# blue-jammer.net
KiCad netlist of a schematic drawn in EasyEDA
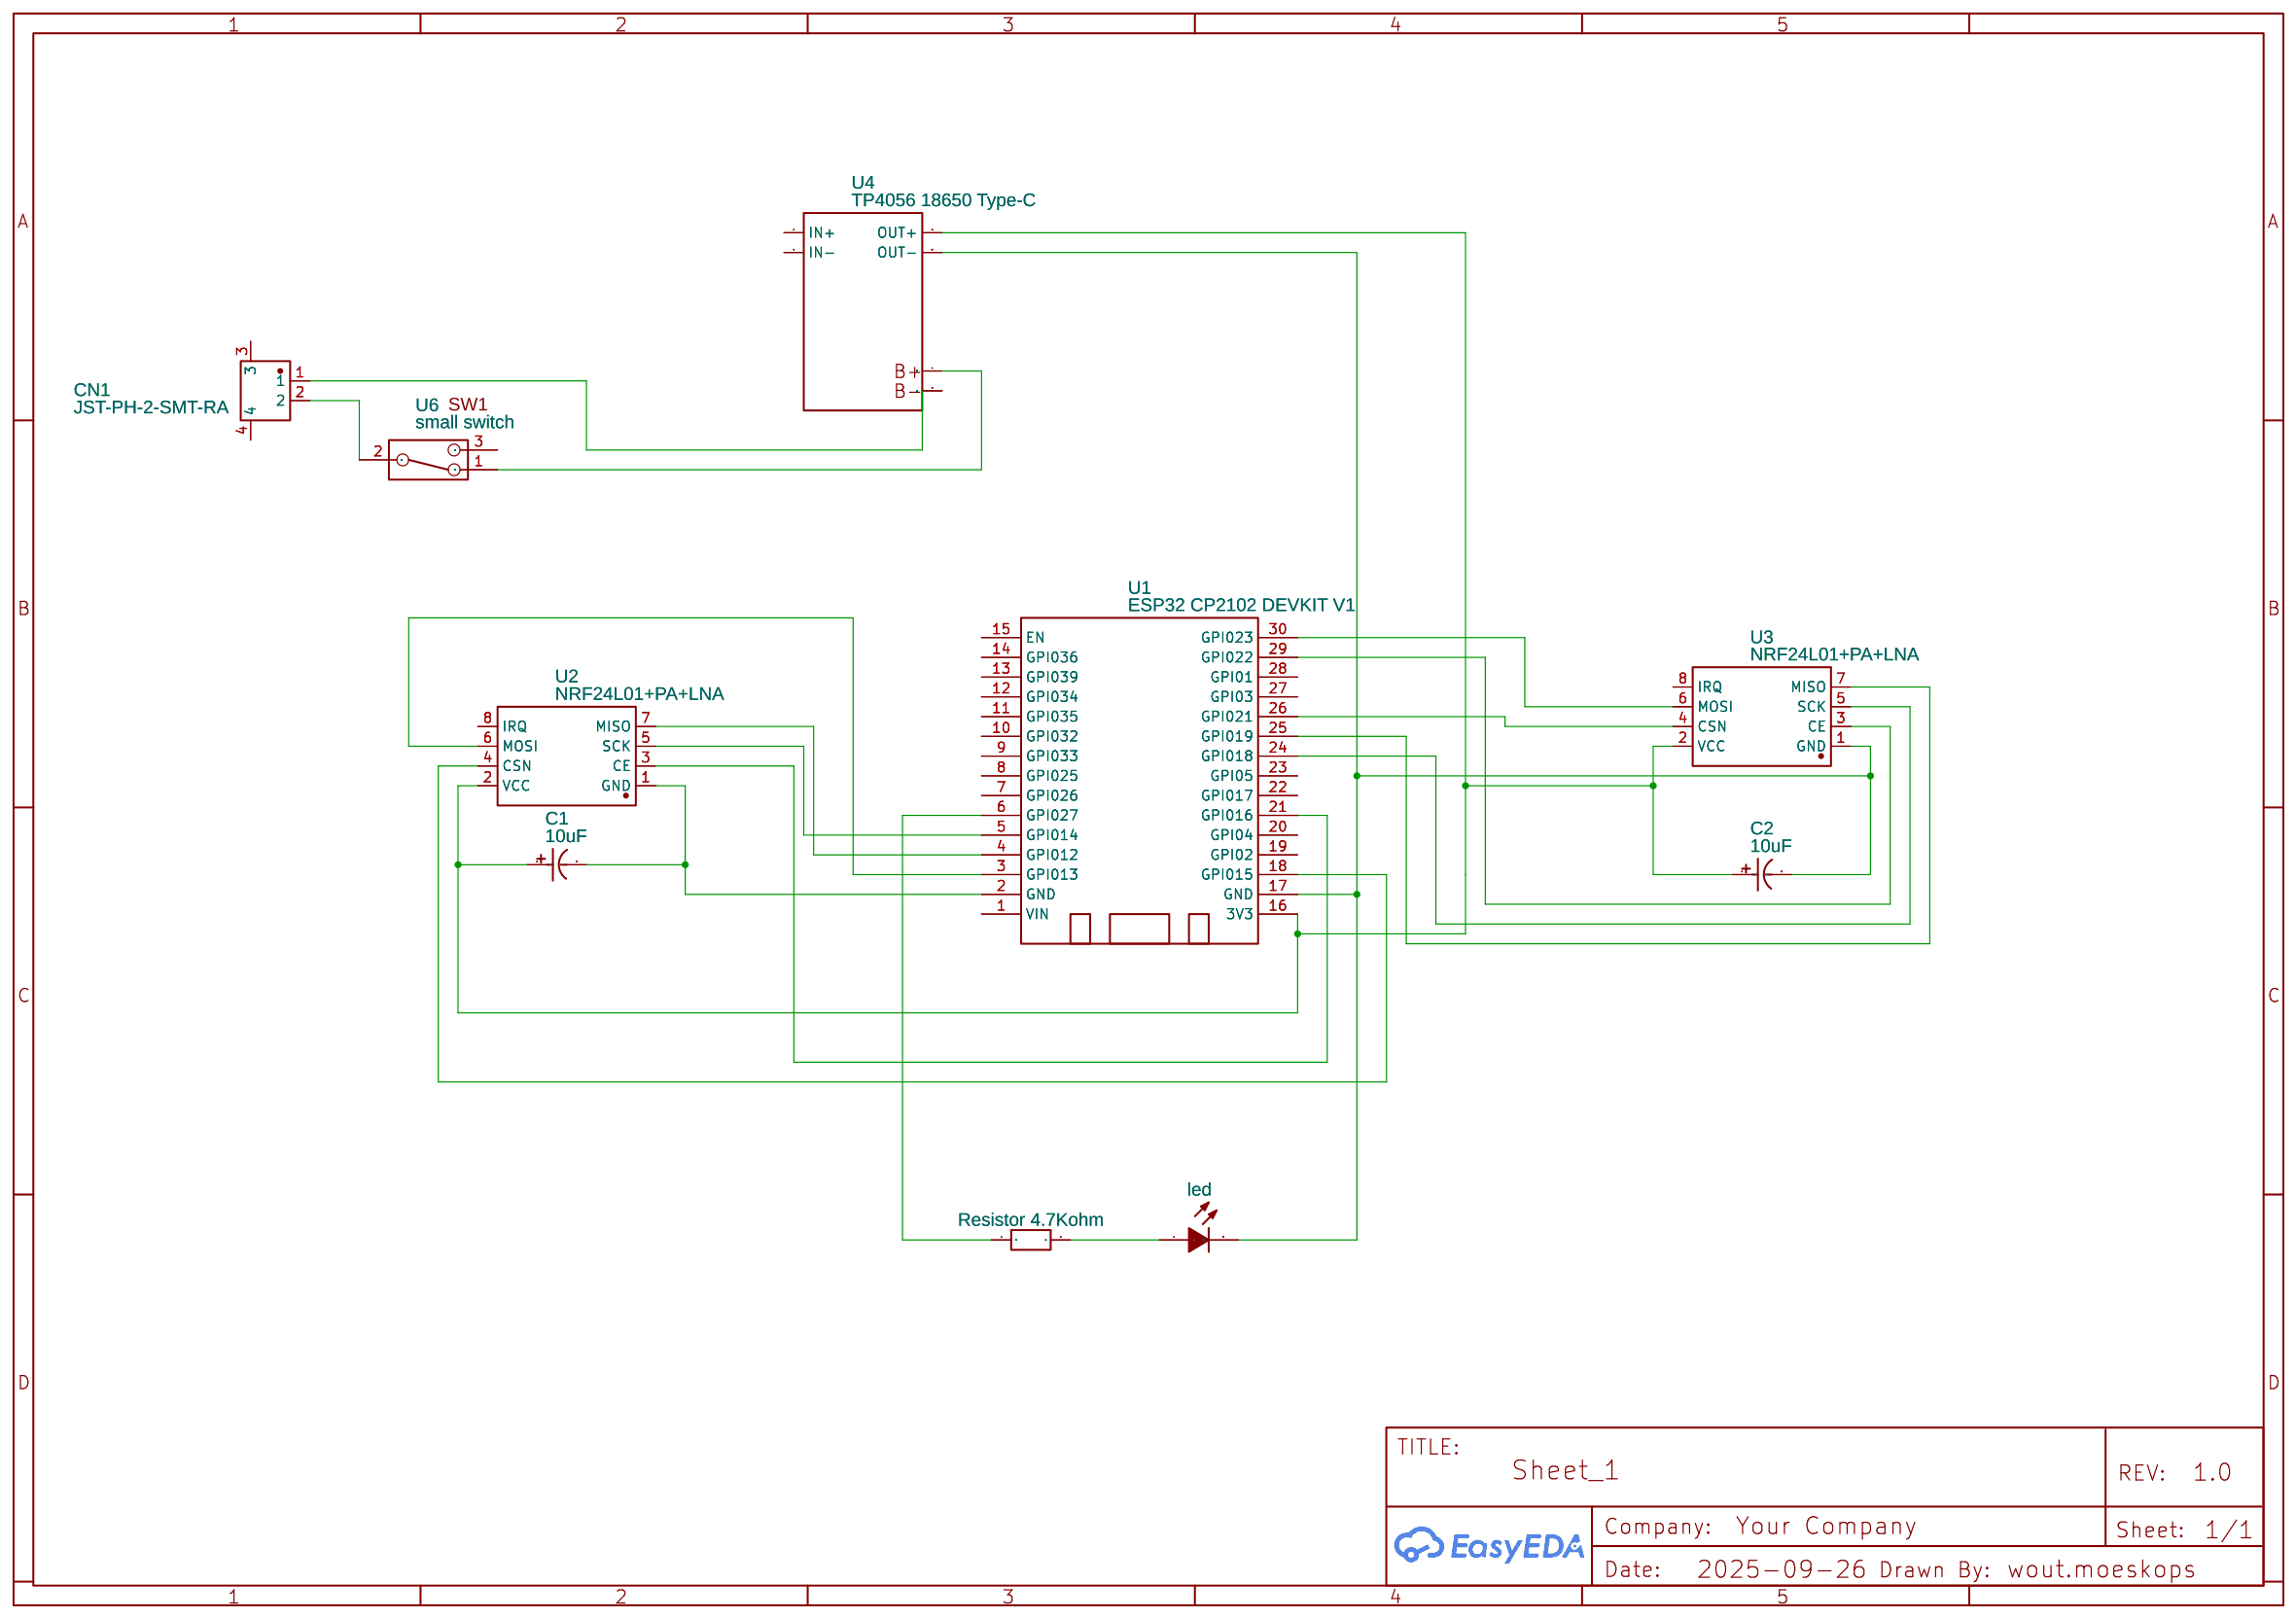
[diagram p0: schematic sheet]

(export (version "E")
  (design (tool "Eeschema 10.0.6"))
  (components
    (comp (ref "C1")
      (value "10uF")
      (fields
        (field (name "Manufacturer Part") "electrolytic capacitor10UF50V")
        (field (name "Manufacturer") "ValuePro")
      )
      (libsource (lib "") (part "10UF 50V CAPACITOR"))
    )
    (comp (ref "C2")
      (value "10uF")
      (fields
        (field (name "Manufacturer Part") "electrolytic capacitor10UF50V")
        (field (name "Manufacturer") "ValuePro")
      )
      (libsource (lib "") (part "10UF 50V CAPACITOR"))
    )
    (comp (ref "CN1") (value "JST-PH-2-SMT-RA") (libsource (lib "") (part "JST-PH-2-SMT-RA")))
    (comp (ref "D2")
      (value "led")
      (fields (field (name "Manufacturer Part") "5600") (field (name "Manufacturer") "VccLite"))
      (libsource (lib "") (part "3mm Green TH LED 5600"))
    )
    (comp (ref "R2")
      (value "Resistor 4.7Kohm")
      (fields (field (name "Manufacturer Part") "EWWR0001J20R0T9") (field (name "Manufacturer") "1"))
      (libsource (lib "") (part "560_Axial_1.2W1%_Tha_239"))
    )
    (comp (ref "U1") (value "ESP32 CP2102 DEVKIT V1") (libsource (lib "") (part "ESP32 CP2102 DEVKIT V1")))
    (comp (ref "U2")
      (value "NRF24L01+PA+LNA")
      (fields (field (name "Manufacturer Part") "nRF24L01+PA+LNA"))
      (libsource (lib "") (part "NRF24L01+PA+LNA"))
    )
    (comp (ref "U3")
      (value "NRF24L01+PA+LNA")
      (fields (field (name "Manufacturer Part") "nRF24L01+PA+LNA"))
      (libsource (lib "") (part "NRF24L01+PA+LNA"))
    )
    (comp (ref "U4") (value "TP4056 18650 Type-C") (libsource (lib "") (part "TP4056 18650 Type-C")))
    (comp (ref "U6") (value "small switch") (libsource (lib "") (part "small switch")))
  )
  (nets
    (net (code "1") (name "Net-(C1-+)") (class "Default")
      (node (ref "C1") (pin "1") (pinfunction "+_1") (pintype "input"))
      (node (ref "C2") (pin "1") (pinfunction "+_1") (pintype "input"))
      (node (ref "U1") (pin "16") (pinfunction "3V3_16") (pintype "bidirectional"))
      (node (ref "U2") (pin "2") (pinfunction "VCC_2") (pintype "unspecified"))
      (node (ref "U3") (pin "2") (pinfunction "VCC_2") (pintype "unspecified"))
      (node (ref "U4") (pin "3") (pinfunction "OUT+_3") (pintype "passive"))
    )
    (net (code "2") (name "Net-(C1--)") (class "Default")
      (node (ref "C1") (pin "2") (pinfunction "-_2") (pintype "input"))
      (node (ref "U1") (pin "2") (pinfunction "GND_2") (pintype "bidirectional"))
      (node (ref "U2") (pin "1") (pinfunction "GND_1") (pintype "unspecified"))
    )
    (net (code "3") (name "Net-(C2--)") (class "Default")
      (node (ref "C2") (pin "2") (pinfunction "-_2") (pintype "input"))
      (node (ref "D2") (pin "2") (pinfunction "K_2") (pintype "input"))
      (node (ref "U1") (pin "17") (pinfunction "GND_17") (pintype "bidirectional"))
      (node (ref "U3") (pin "1") (pinfunction "GND_1") (pintype "unspecified"))
      (node (ref "U4") (pin "6") (pinfunction "OUT-_6") (pintype "passive"))
    )
    (net (code "4") (name "Net-(CN1-Pad2)") (class "Default")
      (node (ref "CN1") (pin "2") (pinfunction "2_2") (pintype "unspecified"))
      (node (ref "U6") (pin "2") (pinfunction "2_2") (pintype "unspecified"))
    )
    (net (code "5") (name "Net-(D2-A)") (class "Default")
      (node (ref "D2") (pin "1") (pinfunction "A_1") (pintype "input"))
      (node (ref "R2") (pin "2") (pinfunction "2_2") (pintype "unspecified"))
    )
    (net (code "6") (name "Net-(U1-GPI012)") (class "Default")
      (node (ref "U1") (pin "4") (pinfunction "GPI012_4") (pintype "bidirectional"))
      (node (ref "U2") (pin "7") (pinfunction "MISO_7") (pintype "unspecified"))
    )
    (net (code "7") (name "Net-(U1-GPI013)") (class "Default")
      (node (ref "U1") (pin "3") (pinfunction "GPI013_3") (pintype "bidirectional"))
      (node (ref "U2") (pin "6") (pinfunction "MOSI_6") (pintype "unspecified"))
    )
    (net (code "8") (name "Net-(U1-GPI014)") (class "Default")
      (node (ref "U1") (pin "5") (pinfunction "GPI014_5") (pintype "bidirectional"))
      (node (ref "U2") (pin "5") (pinfunction "SCK_5") (pintype "unspecified"))
    )
    (net (code "9") (name "Net-(U1-GPI015)") (class "Default")
      (node (ref "U1") (pin "18") (pinfunction "GPI015_18") (pintype "bidirectional"))
      (node (ref "U2") (pin "4") (pinfunction "CSN_4") (pintype "unspecified"))
    )
    (net (code "10") (name "Net-(U1-GPI016)") (class "Default")
      (node (ref "U1") (pin "21") (pinfunction "GPI016_21") (pintype "bidirectional"))
      (node (ref "U2") (pin "3") (pinfunction "CE_3") (pintype "unspecified"))
    )
    (net (code "11") (name "Net-(U1-GPI018)") (class "Default")
      (node (ref "U1") (pin "24") (pinfunction "GPI018_24") (pintype "bidirectional"))
      (node (ref "U3") (pin "5") (pinfunction "SCK_5") (pintype "unspecified"))
    )
    (net (code "12") (name "Net-(U1-GPI019)") (class "Default")
      (node (ref "U1") (pin "25") (pinfunction "GPI019_25") (pintype "bidirectional"))
      (node (ref "U3") (pin "7") (pinfunction "MISO_7") (pintype "unspecified"))
    )
    (net (code "13") (name "Net-(U1-GPI021)") (class "Default")
      (node (ref "U1") (pin "26") (pinfunction "GPI021_26") (pintype "bidirectional"))
      (node (ref "U3") (pin "4") (pinfunction "CSN_4") (pintype "unspecified"))
    )
    (net (code "14") (name "Net-(U1-GPI022)") (class "Default")
      (node (ref "U1") (pin "29") (pinfunction "GPI022_29") (pintype "bidirectional"))
      (node (ref "U3") (pin "3") (pinfunction "CE_3") (pintype "unspecified"))
    )
    (net (code "15") (name "Net-(U1-GPI023)") (class "Default")
      (node (ref "U1") (pin "30") (pinfunction "GPI023_30") (pintype "bidirectional"))
      (node (ref "U3") (pin "6") (pinfunction "MOSI_6") (pintype "unspecified"))
    )
    (net (code "16") (name "Net-(U1-GPI027)") (class "Default")
      (node (ref "R2") (pin "1") (pinfunction "1_1") (pintype "unspecified"))
      (node (ref "U1") (pin "6") (pinfunction "GPI027_6") (pintype "bidirectional"))
    )
    (net (code "17") (name "Net-(U4-BAT+)") (class "Default")
      (node (ref "U4") (pin "4") (pinfunction "BAT+_4") (pintype "unspecified"))
      (node (ref "U6") (pin "1") (pinfunction "1_1") (pintype "unspecified"))
    )
    (net (code "18") (name "Net-(U4-BAT-)") (class "Default")
      (node (ref "CN1") (pin "1") (pinfunction "1_1") (pintype "unspecified"))
      (node (ref "U4") (pin "5") (pinfunction "BAT-_5") (pintype "unspecified"))
    )
    (net (code "19") (name "unconnected-(CN1-Pad3)") (class "Default")
      (node (ref "CN1") (pin "3") (pinfunction "3_3") (pintype "unspecified"))
    )
    (net (code "20") (name "unconnected-(CN1-Pad4)") (class "Default")
      (node (ref "CN1") (pin "4") (pinfunction "4_4") (pintype "unspecified"))
    )
    (net (code "21") (name "unconnected-(U1-EN-Pad15)") (class "Default")
      (node (ref "U1") (pin "15") (pinfunction "EN_15") (pintype "bidirectional"))
    )
    (net (code "22") (name "unconnected-(U1-GPI01-Pad28)") (class "Default")
      (node (ref "U1") (pin "28") (pinfunction "GPI01_28") (pintype "bidirectional"))
    )
    (net (code "23") (name "unconnected-(U1-GPI02-Pad19)") (class "Default")
      (node (ref "U1") (pin "19") (pinfunction "GPI02_19") (pintype "bidirectional"))
    )
    (net (code "24") (name "unconnected-(U1-GPI03-Pad27)") (class "Default")
      (node (ref "U1") (pin "27") (pinfunction "GPI03_27") (pintype "bidirectional"))
    )
    (net (code "25") (name "unconnected-(U1-GPI04-Pad20)") (class "Default")
      (node (ref "U1") (pin "20") (pinfunction "GPI04_20") (pintype "bidirectional"))
    )
    (net (code "26") (name "unconnected-(U1-GPI05-Pad23)") (class "Default")
      (node (ref "U1") (pin "23") (pinfunction "GPI05_23") (pintype "bidirectional"))
    )
    (net (code "27") (name "unconnected-(U1-GPI017-Pad22)") (class "Default")
      (node (ref "U1") (pin "22") (pinfunction "GPI017_22") (pintype "bidirectional"))
    )
    (net (code "28") (name "unconnected-(U1-GPI025-Pad8)") (class "Default")
      (node (ref "U1") (pin "8") (pinfunction "GPI025_8") (pintype "bidirectional"))
    )
    (net (code "29") (name "unconnected-(U1-GPI026-Pad7)") (class "Default")
      (node (ref "U1") (pin "7") (pinfunction "GPI026_7") (pintype "bidirectional"))
    )
    (net (code "30") (name "unconnected-(U1-GPI032-Pad10)") (class "Default")
      (node (ref "U1") (pin "10") (pinfunction "GPI032_10") (pintype "bidirectional"))
    )
    (net (code "31") (name "unconnected-(U1-GPI033-Pad9)") (class "Default")
      (node (ref "U1") (pin "9") (pinfunction "GPI033_9") (pintype "bidirectional"))
    )
    (net (code "32") (name "unconnected-(U1-GPI034-Pad12)") (class "Default")
      (node (ref "U1") (pin "12") (pinfunction "GPI034_12") (pintype "input"))
    )
    (net (code "33") (name "unconnected-(U1-GPI035-Pad11)") (class "Default")
      (node (ref "U1") (pin "11") (pinfunction "GPI035_11") (pintype "input"))
    )
    (net (code "34") (name "unconnected-(U1-GPI036-Pad14)") (class "Default")
      (node (ref "U1") (pin "14") (pinfunction "GPI036_14") (pintype "input"))
    )
    (net (code "35") (name "unconnected-(U1-GPI039-Pad13)") (class "Default")
      (node (ref "U1") (pin "13") (pinfunction "GPI039_13") (pintype "input"))
    )
    (net (code "36") (name "unconnected-(U1-VIN-Pad1)") (class "Default")
      (node (ref "U1") (pin "1") (pinfunction "VIN_1") (pintype "input"))
    )
    (net (code "37") (name "unconnected-(U2-IRQ-Pad8)") (class "Default")
      (node (ref "U2") (pin "8") (pinfunction "IRQ_8") (pintype "unspecified"))
    )
    (net (code "38") (name "unconnected-(U3-IRQ-Pad8)") (class "Default")
      (node (ref "U3") (pin "8") (pinfunction "IRQ_8") (pintype "unspecified"))
    )
    (net (code "39") (name "unconnected-(U4-IN+-Pad1)") (class "Default")
      (node (ref "U4") (pin "1") (pinfunction "IN+_1") (pintype "passive"))
    )
    (net (code "40") (name "unconnected-(U4-IN--Pad2)") (class "Default")
      (node (ref "U4") (pin "2") (pinfunction "IN-_2") (pintype "passive"))
    )
    (net (code "41") (name "unconnected-(U6-Pad3)") (class "Default")
      (node (ref "U6") (pin "3") (pinfunction "3_3") (pintype "unspecified"))
    )
  )
)
